# ws2812_Triangle_V04.net
KiCad netlist of a schematic drawn in EAGLE
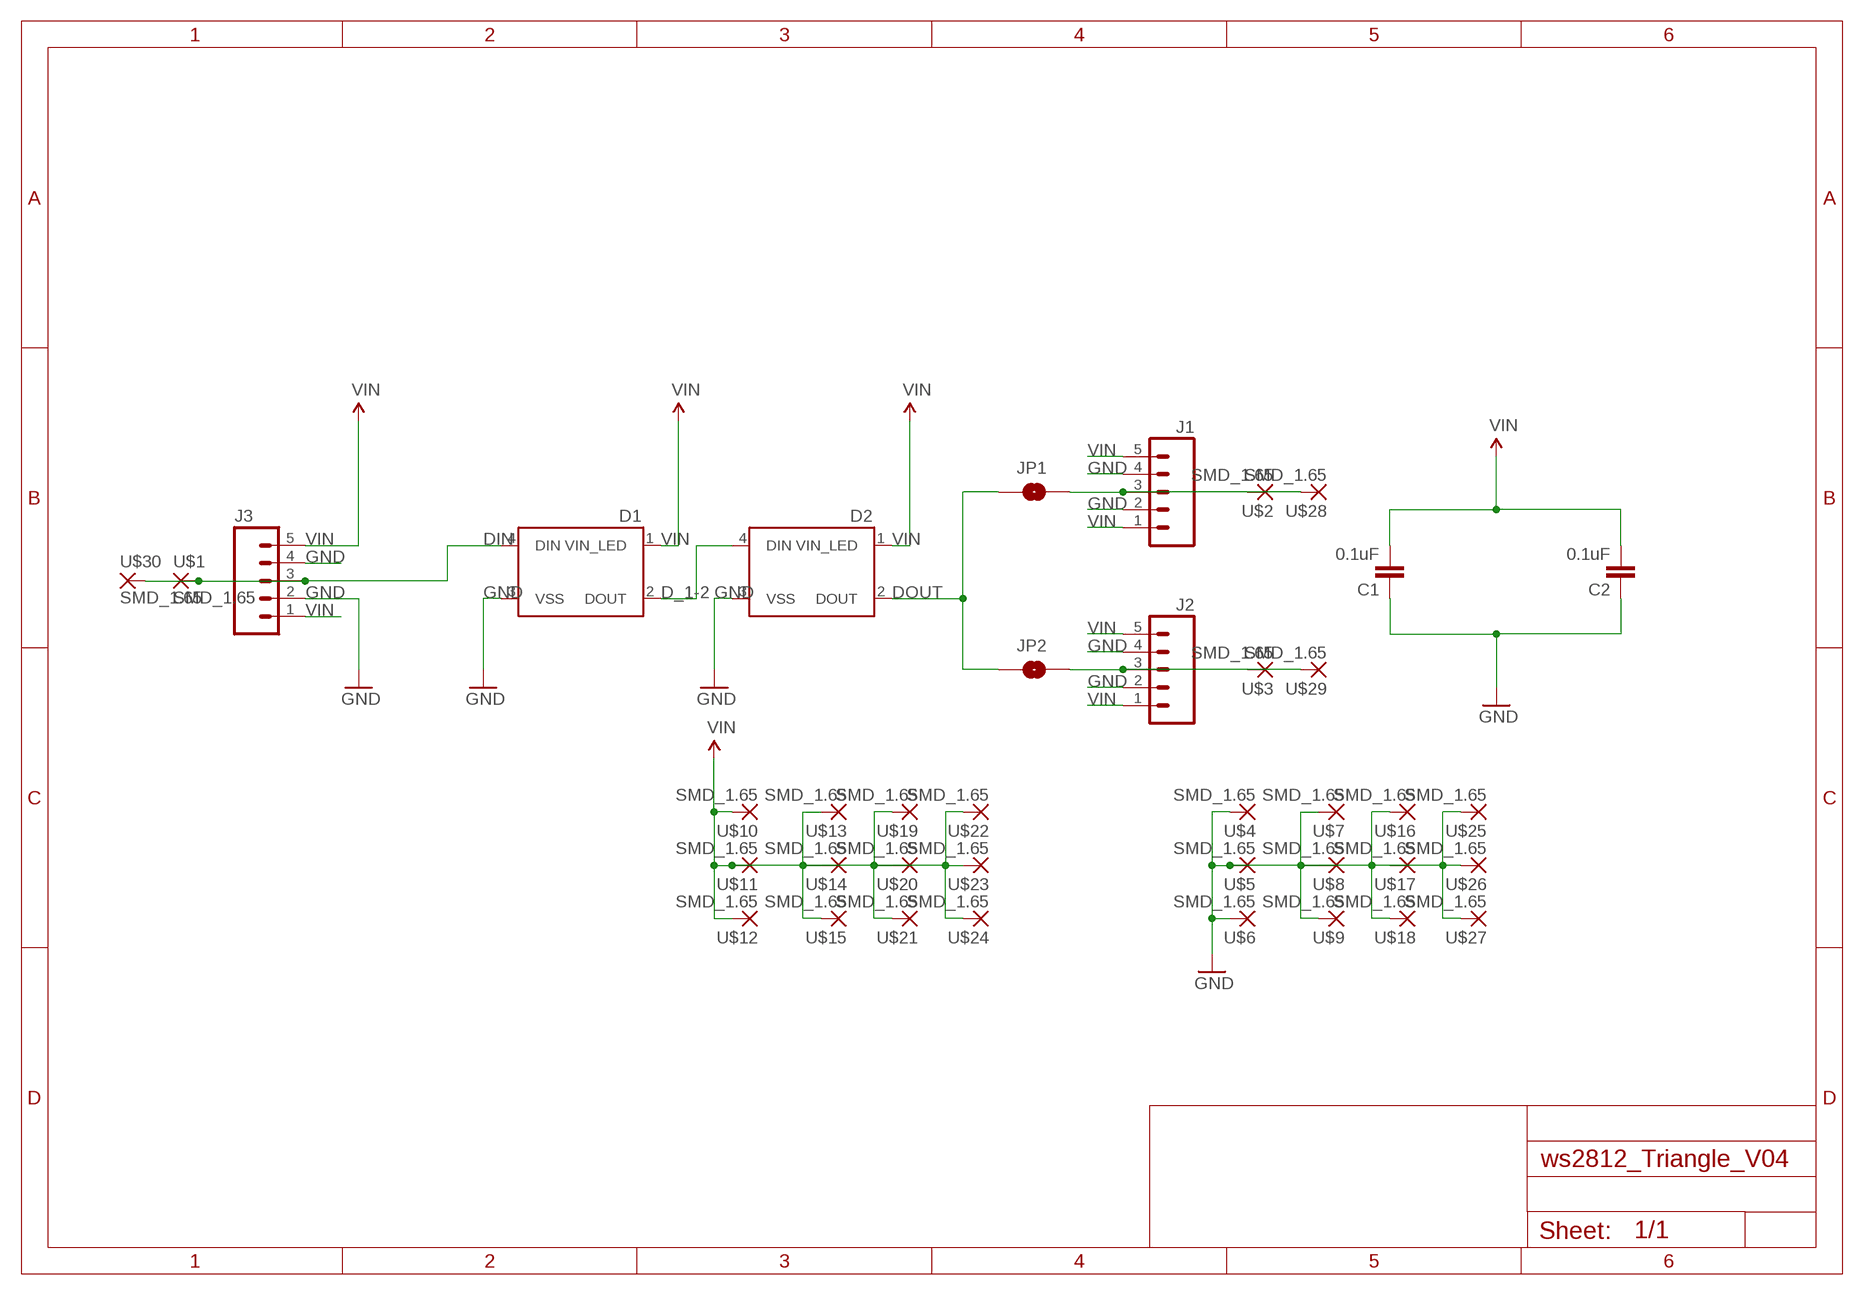
[diagram p0: schematic, sheet 1]

(export (version "E")
  (design (tool "Eeschema 10.0.6"))
  (components
    (comp (ref "C1")
      (value "0.1uF")
      (footprint "eagle-import:0805")
      (libsource (lib "eagle-import") (part "CAP0805"))
    )
    (comp (ref "C2")
      (value "0.1uF")
      (footprint "eagle-import:0805")
      (libsource (lib "eagle-import") (part "CAP0805"))
    )
    (comp (ref "D1")
      (value "WS2812B")
      (footprint "eagle-import:WS2812B")
      (libsource (lib "eagle-import") (part "WS2812B"))
    )
    (comp (ref "D2")
      (value "WS2812B")
      (footprint "eagle-import:WS2812B")
      (libsource (lib "eagle-import") (part "WS2812B"))
    )
    (comp (ref "J1")
      (value "M05NO_SILK")
      (footprint "eagle-import:1X05_NO_SILK")
      (libsource (lib "eagle-import") (part "M05NO_SILK"))
    )
    (comp (ref "J2")
      (value "M05NO_SILK")
      (footprint "eagle-import:1X05_NO_SILK")
      (libsource (lib "eagle-import") (part "M05NO_SILK"))
    )
    (comp (ref "J3")
      (value "M05NO_SILK")
      (footprint "eagle-import:1X05_NO_SILK")
      (libsource (lib "eagle-import") (part "M05NO_SILK"))
    )
    (comp (ref "JP1")
      (value "JUMPER-PAD-2-NOYES_SILK")
      (footprint "eagle-import:PAD-JUMPER-2-NO_YES_SILK")
      (libsource (lib "eagle-import") (part "JUMPER-PAD-2-NOYES_SILK"))
    )
    (comp (ref "JP2")
      (value "JUMPER-PAD-2-NOYES_SILK")
      (footprint "eagle-import:PAD-JUMPER-2-NO_YES_SILK")
      (libsource (lib "eagle-import") (part "JUMPER-PAD-2-NOYES_SILK"))
    )
    (comp (ref "U$1")
      (value "SMD_1.65")
      (footprint "eagle-import:SMD_PTH_1.65")
      (libsource (lib "eagle-import") (part "SMD_1.65"))
    )
    (comp (ref "U$2")
      (value "SMD_1.65")
      (footprint "eagle-import:SMD_PTH_1.65")
      (libsource (lib "eagle-import") (part "SMD_1.65"))
    )
    (comp (ref "U$3")
      (value "SMD_1.65")
      (footprint "eagle-import:SMD_PTH_1.65")
      (libsource (lib "eagle-import") (part "SMD_1.65"))
    )
    (comp (ref "U$4")
      (value "SMD_1.65")
      (footprint "eagle-import:SMD_PTH_1.65")
      (libsource (lib "eagle-import") (part "SMD_1.65"))
    )
    (comp (ref "U$5")
      (value "SMD_1.65")
      (footprint "eagle-import:SMD_PTH_1.65")
      (libsource (lib "eagle-import") (part "SMD_1.65"))
    )
    (comp (ref "U$6")
      (value "SMD_1.65")
      (footprint "eagle-import:SMD_PTH_1.65")
      (libsource (lib "eagle-import") (part "SMD_1.65"))
    )
    (comp (ref "U$7")
      (value "SMD_1.65")
      (footprint "eagle-import:SMD_PTH_1.65")
      (libsource (lib "eagle-import") (part "SMD_1.65"))
    )
    (comp (ref "U$8")
      (value "SMD_1.65")
      (footprint "eagle-import:SMD_PTH_1.65")
      (libsource (lib "eagle-import") (part "SMD_1.65"))
    )
    (comp (ref "U$9")
      (value "SMD_1.65")
      (footprint "eagle-import:SMD_PTH_1.65")
      (libsource (lib "eagle-import") (part "SMD_1.65"))
    )
    (comp (ref "U$10")
      (value "SMD_1.65")
      (footprint "eagle-import:SMD_PTH_1.65")
      (libsource (lib "eagle-import") (part "SMD_1.65"))
    )
    (comp (ref "U$11")
      (value "SMD_1.65")
      (footprint "eagle-import:SMD_PTH_1.65")
      (libsource (lib "eagle-import") (part "SMD_1.65"))
    )
    (comp (ref "U$12")
      (value "SMD_1.65")
      (footprint "eagle-import:SMD_PTH_1.65")
      (libsource (lib "eagle-import") (part "SMD_1.65"))
    )
    (comp (ref "U$13")
      (value "SMD_1.65")
      (footprint "eagle-import:SMD_PTH_1.65")
      (libsource (lib "eagle-import") (part "SMD_1.65"))
    )
    (comp (ref "U$14")
      (value "SMD_1.65")
      (footprint "eagle-import:SMD_PTH_1.65")
      (libsource (lib "eagle-import") (part "SMD_1.65"))
    )
    (comp (ref "U$15")
      (value "SMD_1.65")
      (footprint "eagle-import:SMD_PTH_1.65")
      (libsource (lib "eagle-import") (part "SMD_1.65"))
    )
    (comp (ref "U$16")
      (value "SMD_1.65")
      (footprint "eagle-import:SMD_PTH_1.65")
      (libsource (lib "eagle-import") (part "SMD_1.65"))
    )
    (comp (ref "U$17")
      (value "SMD_1.65")
      (footprint "eagle-import:SMD_PTH_1.65")
      (libsource (lib "eagle-import") (part "SMD_1.65"))
    )
    (comp (ref "U$18")
      (value "SMD_1.65")
      (footprint "eagle-import:SMD_PTH_1.65")
      (libsource (lib "eagle-import") (part "SMD_1.65"))
    )
    (comp (ref "U$19")
      (value "SMD_1.65")
      (footprint "eagle-import:SMD_PTH_1.65")
      (libsource (lib "eagle-import") (part "SMD_1.65"))
    )
    (comp (ref "U$20")
      (value "SMD_1.65")
      (footprint "eagle-import:SMD_PTH_1.65")
      (libsource (lib "eagle-import") (part "SMD_1.65"))
    )
    (comp (ref "U$21")
      (value "SMD_1.65")
      (footprint "eagle-import:SMD_PTH_1.65")
      (libsource (lib "eagle-import") (part "SMD_1.65"))
    )
    (comp (ref "U$22")
      (value "SMD_1.65")
      (footprint "eagle-import:SMD_PTH_1.65")
      (libsource (lib "eagle-import") (part "SMD_1.65"))
    )
    (comp (ref "U$23")
      (value "SMD_1.65")
      (footprint "eagle-import:SMD_PTH_1.65")
      (libsource (lib "eagle-import") (part "SMD_1.65"))
    )
    (comp (ref "U$24")
      (value "SMD_1.65")
      (footprint "eagle-import:SMD_PTH_1.65")
      (libsource (lib "eagle-import") (part "SMD_1.65"))
    )
    (comp (ref "U$25")
      (value "SMD_1.65")
      (footprint "eagle-import:SMD_PTH_1.65")
      (libsource (lib "eagle-import") (part "SMD_1.65"))
    )
    (comp (ref "U$26")
      (value "SMD_1.65")
      (footprint "eagle-import:SMD_PTH_1.65")
      (libsource (lib "eagle-import") (part "SMD_1.65"))
    )
    (comp (ref "U$27")
      (value "SMD_1.65")
      (footprint "eagle-import:SMD_PTH_1.65")
      (libsource (lib "eagle-import") (part "SMD_1.65"))
    )
    (comp (ref "U$28")
      (value "SMD_1.65")
      (footprint "eagle-import:SMD_PTH_1.65")
      (libsource (lib "eagle-import") (part "SMD_1.65"))
    )
    (comp (ref "U$29")
      (value "SMD_1.65")
      (footprint "eagle-import:SMD_PTH_1.65")
      (libsource (lib "eagle-import") (part "SMD_1.65"))
    )
    (comp (ref "U$30")
      (value "SMD_1.65")
      (footprint "eagle-import:SMD_PTH_1.65")
      (libsource (lib "eagle-import") (part "SMD_1.65"))
    )
  )
  (nets
    (net (code "1") (name "/DIN") (class "Default")
      (node (ref "D1") (pin "4") (pinfunction "DIN_4") (pintype "input"))
      (node (ref "J3") (pin "3") (pinfunction "3_3") (pintype "passive"))
      (node (ref "U$1") (pin "P$1") (pinfunction "P_P$1") (pintype "passive"))
      (node (ref "U$30") (pin "P$1") (pinfunction "P_P$1") (pintype "passive"))
    )
    (net (code "2") (name "/DOUT") (class "Default")
      (node (ref "D2") (pin "2") (pinfunction "DOUT_2") (pintype "output"))
      (node (ref "JP1") (pin "1") (pinfunction "1_1") (pintype "passive"))
      (node (ref "JP2") (pin "1") (pinfunction "1_1") (pintype "passive"))
    )
    (net (code "3") (name "/D_1-2") (class "Default")
      (node (ref "D1") (pin "2") (pinfunction "DOUT_2") (pintype "output"))
      (node (ref "D2") (pin "4") (pinfunction "DIN_4") (pintype "input"))
    )
    (net (code "4") (name "GND") (class "Default")
      (node (ref "C1") (pin "1") (pinfunction "1_1") (pintype "passive"))
      (node (ref "C2") (pin "1") (pinfunction "1_1") (pintype "passive"))
      (node (ref "D1") (pin "3") (pinfunction "VSS_3") (pintype "power_in"))
      (node (ref "D2") (pin "3") (pinfunction "VSS_3") (pintype "power_in"))
      (node (ref "J1") (pin "2") (pinfunction "2_2") (pintype "passive"))
      (node (ref "J1") (pin "4") (pinfunction "4_4") (pintype "passive"))
      (node (ref "J2") (pin "2") (pinfunction "2_2") (pintype "passive"))
      (node (ref "J2") (pin "4") (pinfunction "4_4") (pintype "passive"))
      (node (ref "J3") (pin "2") (pinfunction "2_2") (pintype "passive"))
      (node (ref "J3") (pin "4") (pinfunction "4_4") (pintype "passive"))
      (node (ref "U$16") (pin "P$1") (pinfunction "P_P$1") (pintype "passive"))
      (node (ref "U$17") (pin "P$1") (pinfunction "P_P$1") (pintype "passive"))
      (node (ref "U$18") (pin "P$1") (pinfunction "P_P$1") (pintype "passive"))
      (node (ref "U$25") (pin "P$1") (pinfunction "P_P$1") (pintype "passive"))
      (node (ref "U$26") (pin "P$1") (pinfunction "P_P$1") (pintype "passive"))
      (node (ref "U$27") (pin "P$1") (pinfunction "P_P$1") (pintype "passive"))
      (node (ref "U$4") (pin "P$1") (pinfunction "P_P$1") (pintype "passive"))
      (node (ref "U$5") (pin "P$1") (pinfunction "P_P$1") (pintype "passive"))
      (node (ref "U$6") (pin "P$1") (pinfunction "P_P$1") (pintype "passive"))
      (node (ref "U$7") (pin "P$1") (pinfunction "P_P$1") (pintype "passive"))
      (node (ref "U$8") (pin "P$1") (pinfunction "P_P$1") (pintype "passive"))
      (node (ref "U$9") (pin "P$1") (pinfunction "P_P$1") (pintype "passive"))
    )
    (net (code "5") (name "Net-(U$2-P)") (class "Default")
      (node (ref "J1") (pin "3") (pinfunction "3_3") (pintype "passive"))
      (node (ref "JP1") (pin "2") (pinfunction "2_2") (pintype "passive"))
      (node (ref "U$2") (pin "P$1") (pinfunction "P_P$1") (pintype "passive"))
      (node (ref "U$28") (pin "P$1") (pinfunction "P_P$1") (pintype "passive"))
    )
    (net (code "6") (name "Net-(U$29-P)") (class "Default")
      (node (ref "J2") (pin "3") (pinfunction "3_3") (pintype "passive"))
      (node (ref "JP2") (pin "2") (pinfunction "2_2") (pintype "passive"))
      (node (ref "U$29") (pin "P$1") (pinfunction "P_P$1") (pintype "passive"))
      (node (ref "U$3") (pin "P$1") (pinfunction "P_P$1") (pintype "passive"))
    )
    (net (code "7") (name "VIN") (class "Default")
      (node (ref "C1") (pin "2") (pinfunction "2_2") (pintype "passive"))
      (node (ref "C2") (pin "2") (pinfunction "2_2") (pintype "passive"))
      (node (ref "D1") (pin "1") (pinfunction "VIN_LED_1") (pintype "power_in"))
      (node (ref "D2") (pin "1") (pinfunction "VIN_LED_1") (pintype "power_in"))
      (node (ref "J1") (pin "1") (pinfunction "1_1") (pintype "passive"))
      (node (ref "J1") (pin "5") (pinfunction "5_5") (pintype "passive"))
      (node (ref "J2") (pin "1") (pinfunction "1_1") (pintype "passive"))
      (node (ref "J2") (pin "5") (pinfunction "5_5") (pintype "passive"))
      (node (ref "J3") (pin "1") (pinfunction "1_1") (pintype "passive"))
      (node (ref "J3") (pin "5") (pinfunction "5_5") (pintype "passive"))
      (node (ref "U$10") (pin "P$1") (pinfunction "P_P$1") (pintype "passive"))
      (node (ref "U$11") (pin "P$1") (pinfunction "P_P$1") (pintype "passive"))
      (node (ref "U$12") (pin "P$1") (pinfunction "P_P$1") (pintype "passive"))
      (node (ref "U$13") (pin "P$1") (pinfunction "P_P$1") (pintype "passive"))
      (node (ref "U$14") (pin "P$1") (pinfunction "P_P$1") (pintype "passive"))
      (node (ref "U$15") (pin "P$1") (pinfunction "P_P$1") (pintype "passive"))
      (node (ref "U$19") (pin "P$1") (pinfunction "P_P$1") (pintype "passive"))
      (node (ref "U$20") (pin "P$1") (pinfunction "P_P$1") (pintype "passive"))
      (node (ref "U$21") (pin "P$1") (pinfunction "P_P$1") (pintype "passive"))
      (node (ref "U$22") (pin "P$1") (pinfunction "P_P$1") (pintype "passive"))
      (node (ref "U$23") (pin "P$1") (pinfunction "P_P$1") (pintype "passive"))
      (node (ref "U$24") (pin "P$1") (pinfunction "P_P$1") (pintype "passive"))
    )
  )
)
